# Ideamart-NB-IoT-Air-Quality-Sensor-v1.net
KiCad netlist of a schematic drawn in EAGLE
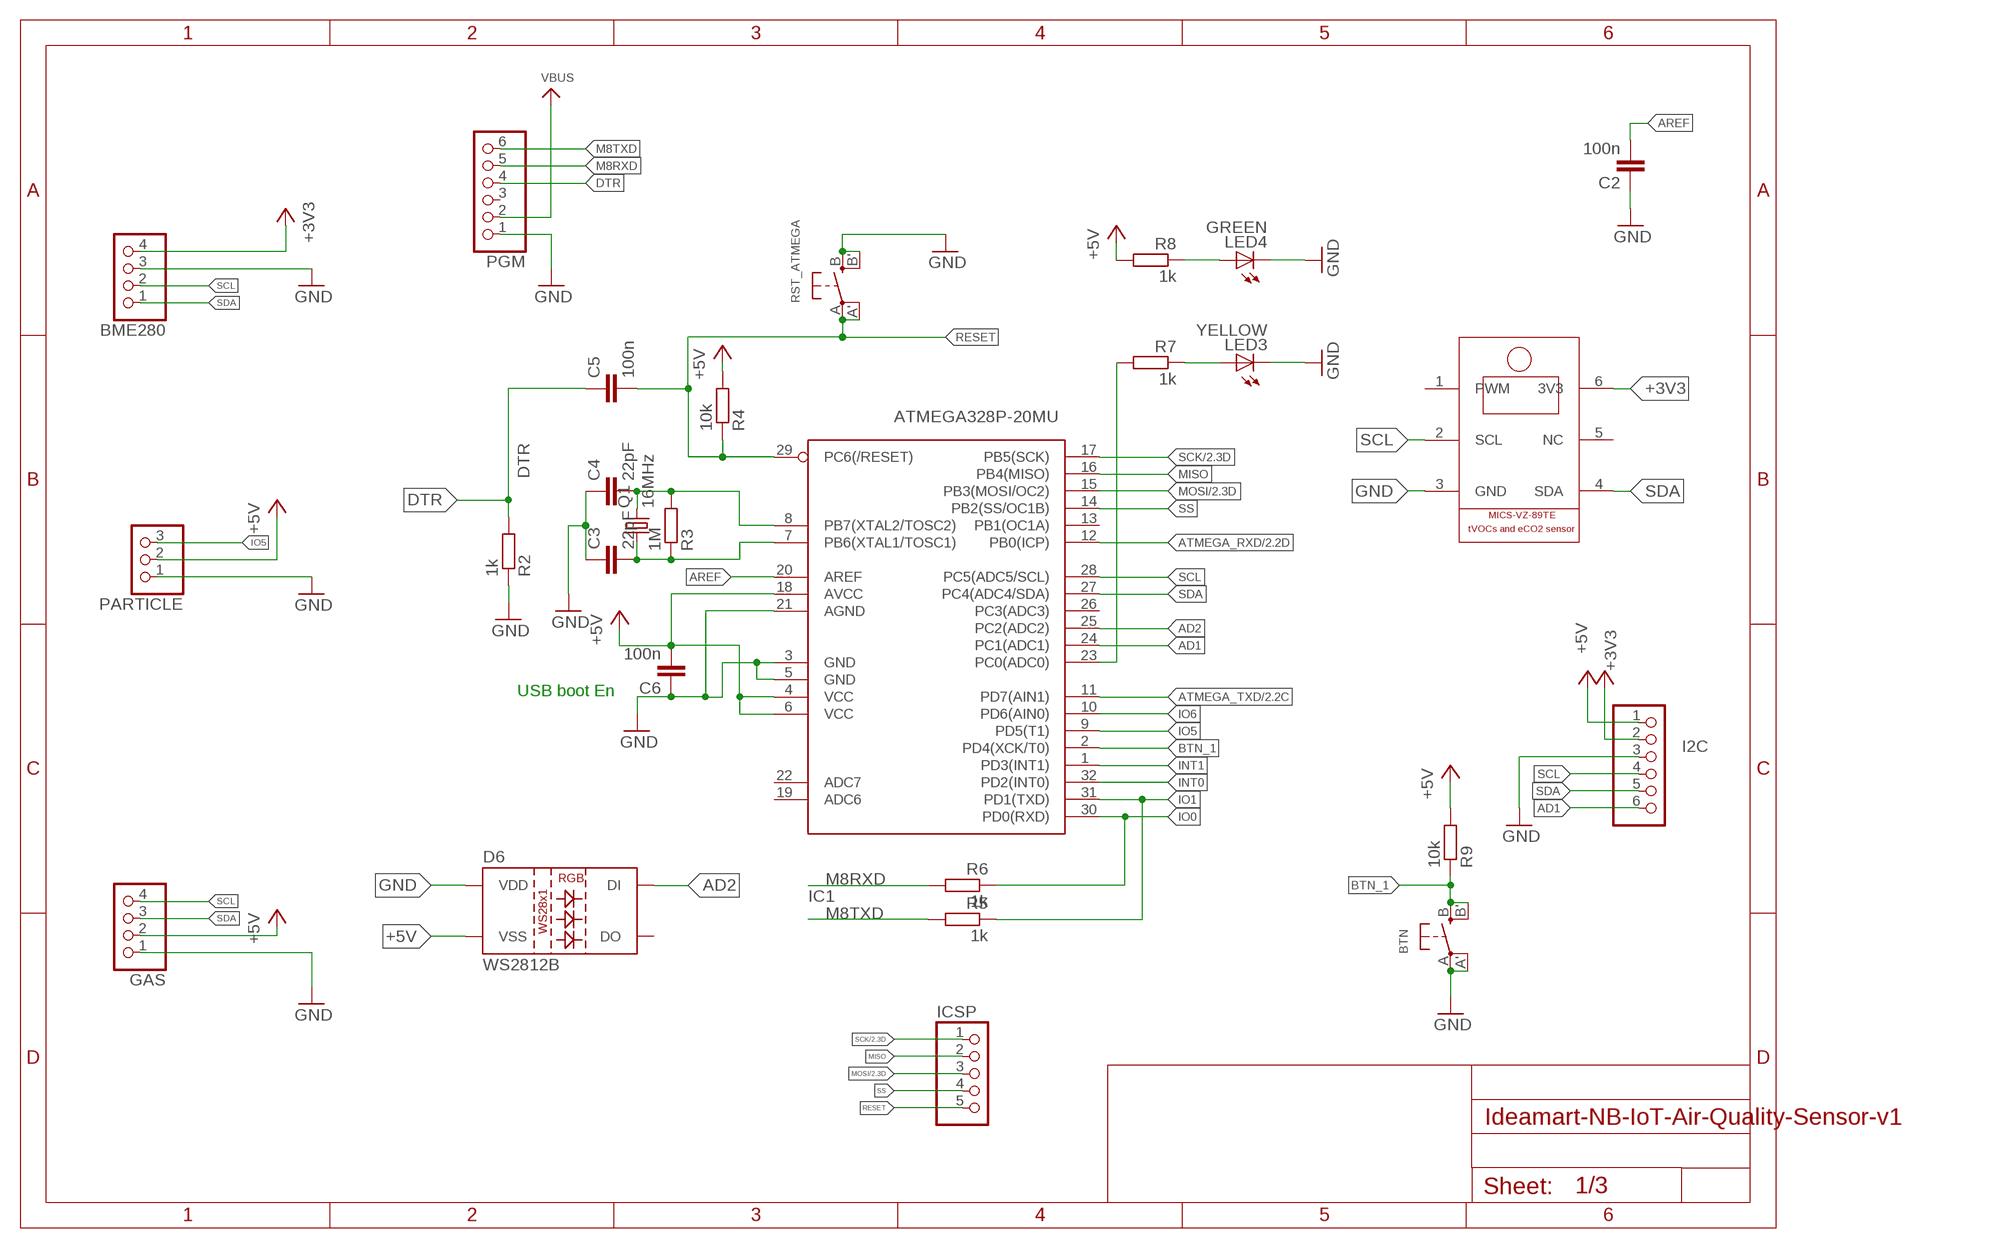
[diagram p0: schematic, sheet 1]
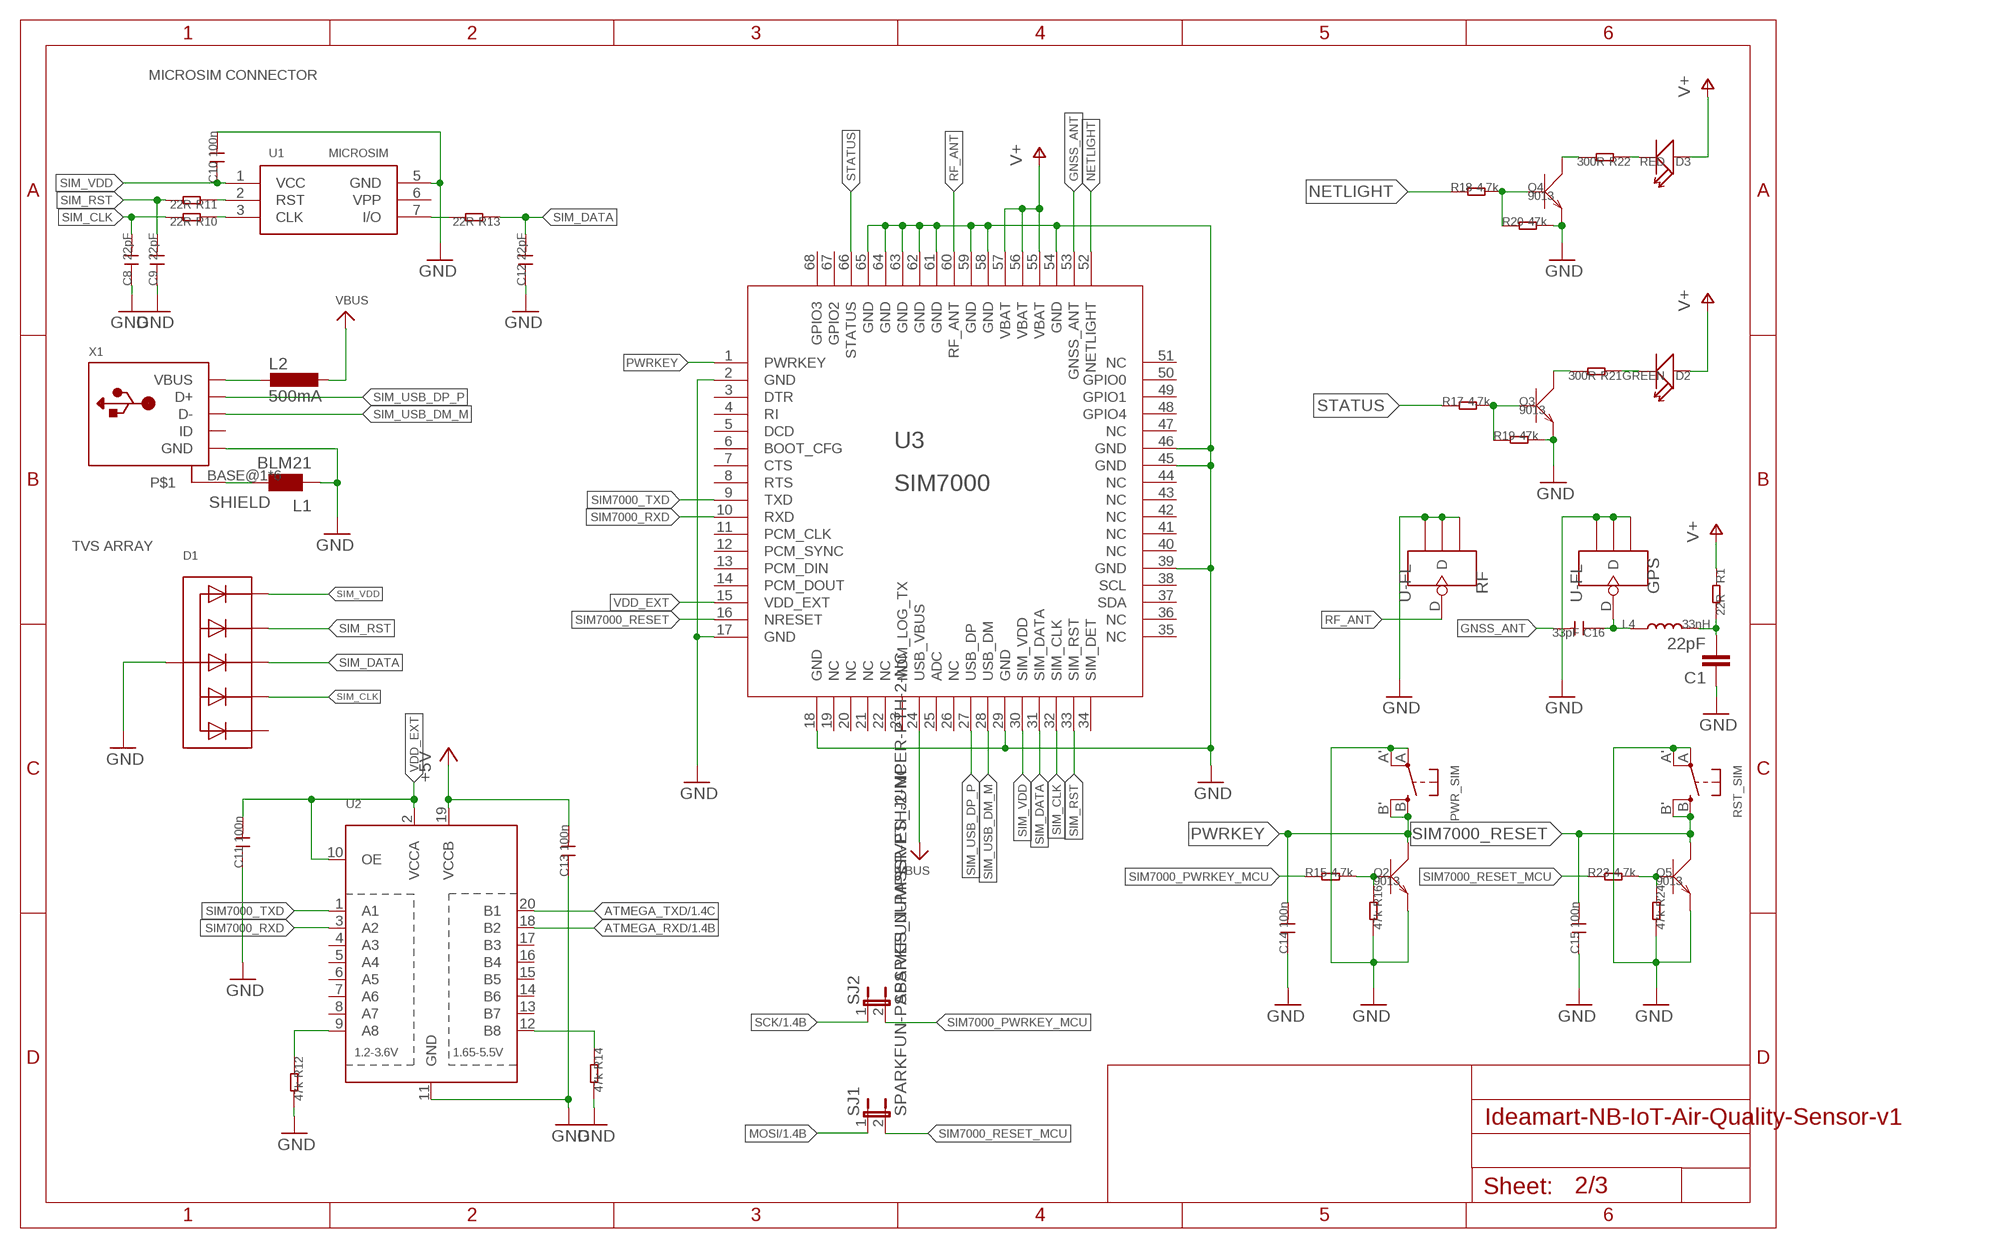
[diagram p1: schematic, sheet 2]
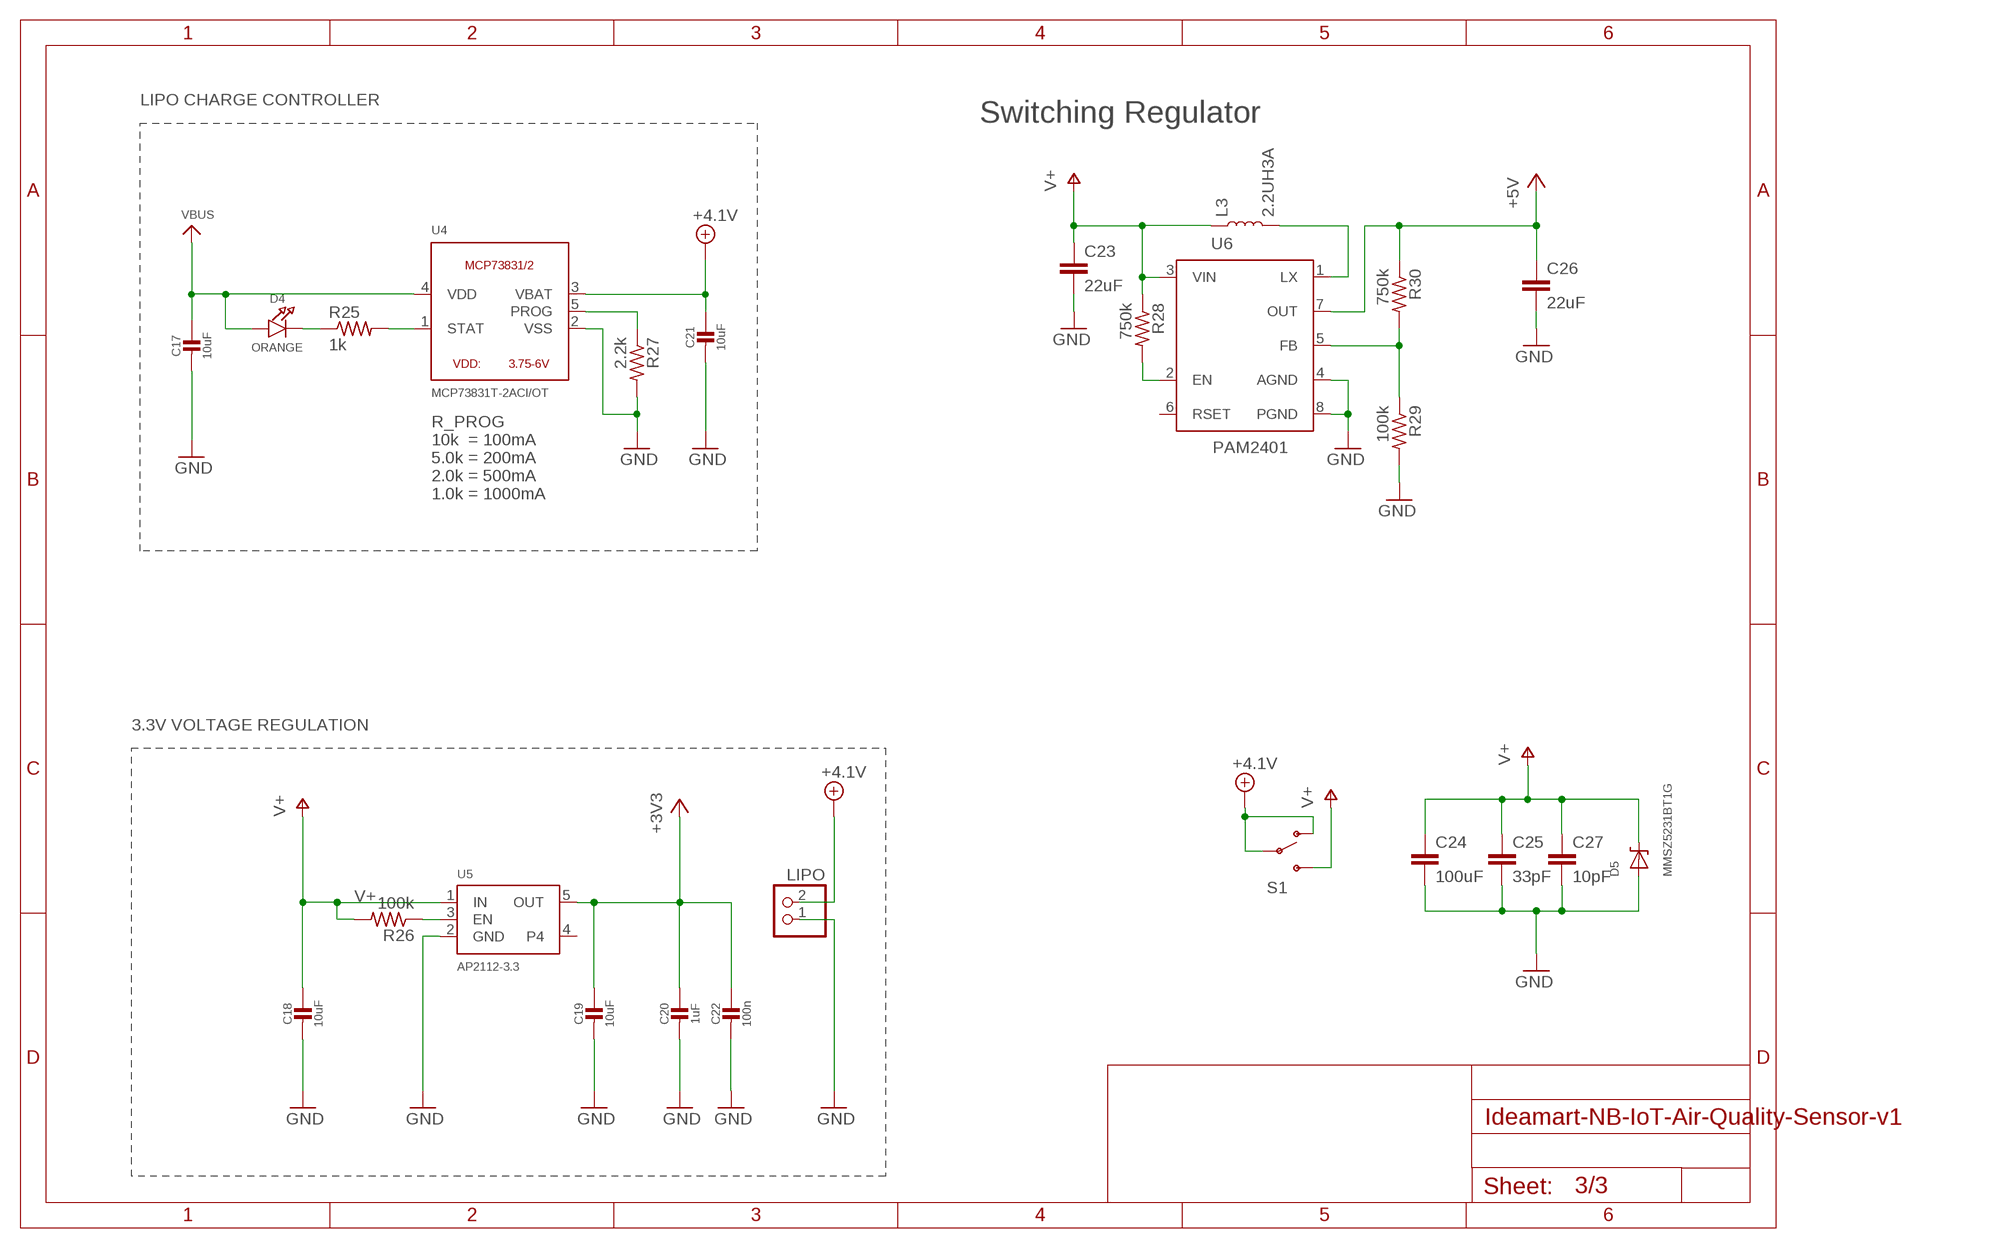
[diagram p2: schematic, sheet 3]

(export (version "E")
  (design (tool "Eeschema 10.0.6"))
  (components
    (comp (ref "BME280")
      (value "PINHD-1X4")
      (footprint "eagle-import:1X04")
      (libsource (lib "eagle-import") (part "PINHD-1X4"))
    )
    (comp (ref "BTN")
      (value "SWITCH_TACT_SMT4.6X2.8")
      (footprint "eagle-import:BTN_KMR2_4.6X2.8")
      (libsource (lib "eagle-import") (part "SWITCH_TACT_SMT4.6X2.8"))
    )
    (comp (ref "C2")
      (value "100n")
      (footprint "eagle-import:C0805")
      (libsource (lib "eagle-import") (part "C-EUC0805"))
    )
    (comp (ref "C3")
      (value "22pF")
      (footprint "eagle-import:C0805")
      (libsource (lib "eagle-import") (part "C-EUC0805"))
    )
    (comp (ref "C4")
      (value "22pF")
      (footprint "eagle-import:C0805")
      (libsource (lib "eagle-import") (part "C-EUC0805"))
    )
    (comp (ref "C5")
      (value "100n")
      (footprint "eagle-import:C0805")
      (libsource (lib "eagle-import") (part "C-EUC0805"))
    )
    (comp (ref "C6")
      (value "100n")
      (footprint "eagle-import:C0805")
      (libsource (lib "eagle-import") (part "C-EUC0805"))
    )
    (comp (ref "D6")
      (value "WS2812B")
      (footprint "eagle-import:WS2812B")
      (libsource (lib "eagle-import") (part "WS2812B"))
    )
    (comp (ref "GAS")
      (value "PINHD-1X4")
      (footprint "eagle-import:1X04")
      (libsource (lib "eagle-import") (part "PINHD-1X4"))
    )
    (comp (ref "I2C")
      (value "PINHD-1X6")
      (footprint "eagle-import:1X06")
      (libsource (lib "eagle-import") (part "PINHD-1X6"))
    )
    (comp (ref "IC1")
      (value "ATMEGA328P-20MU")
      (footprint "eagle-import:TQFP32-08")
      (libsource (lib "eagle-import") (part "MEGA8-AI"))
    )
    (comp (ref "ICSP")
      (value "PINHD-1X5")
      (footprint "eagle-import:1X05")
      (libsource (lib "eagle-import") (part "PINHD-1X5"))
    )
    (comp (ref "LED3")
      (value "YELLOW")
      (footprint "eagle-import:CHIP-LED0805")
      (libsource (lib "eagle-import") (part "LEDCHIP-LED0805"))
    )
    (comp (ref "LED4")
      (value "GREEN")
      (footprint "eagle-import:CHIP-LED0805")
      (libsource (lib "eagle-import") (part "LEDCHIP-LED0805"))
    )
    (comp (ref "PARTICLE")
      (value "PINHD-1X3")
      (footprint "eagle-import:1X03")
      (libsource (lib "eagle-import") (part "PINHD-1X3"))
    )
    (comp (ref "PGM")
      (value "PINHD-1X6")
      (footprint "eagle-import:1X06")
      (libsource (lib "eagle-import") (part "PINHD-1X6"))
    )
    (comp (ref "Q1")
      (value "16MHz")
      (footprint "eagle-import:CTS406")
      (libsource (lib "eagle-import") (part "CRYSTALCTS406"))
    )
    (comp (ref "R2")
      (value "1k")
      (footprint "eagle-import:R0805")
      (libsource (lib "eagle-import") (part "R-EU_R0805"))
    )
    (comp (ref "R3")
      (value "1M")
      (footprint "eagle-import:R0805")
      (libsource (lib "eagle-import") (part "R-EU_R0805"))
    )
    (comp (ref "R4")
      (value "10k")
      (footprint "eagle-import:R0805")
      (libsource (lib "eagle-import") (part "R-EU_R0805"))
    )
    (comp (ref "R5")
      (value "1k")
      (footprint "eagle-import:R0805")
      (libsource (lib "eagle-import") (part "R-EU_R0805"))
    )
    (comp (ref "R6")
      (value "1k")
      (footprint "eagle-import:R0805")
      (libsource (lib "eagle-import") (part "R-EU_R0805"))
    )
    (comp (ref "R7")
      (value "1k")
      (footprint "eagle-import:R0805")
      (libsource (lib "eagle-import") (part "R-EU_R0805"))
    )
    (comp (ref "R8")
      (value "1k")
      (footprint "eagle-import:R0805")
      (libsource (lib "eagle-import") (part "R-EU_R0805"))
    )
    (comp (ref "R9")
      (value "10k")
      (footprint "eagle-import:R0805")
      (libsource (lib "eagle-import") (part "R-EU_R0805"))
    )
    (comp (ref "RST_ATMEGA")
      (value "SWITCH_TACT_SMT4.6X2.8")
      (footprint "eagle-import:BTN_KMR2_4.6X2.8")
      (libsource (lib "eagle-import") (part "SWITCH_TACT_SMT4.6X2.8"))
    )
    (comp (ref "U$1")
      (value "MICS-VZ-89TE")
      (footprint "eagle-import:MICS-VZ-89TE")
      (libsource (lib "eagle-import") (part "MICS-VZ-89TE"))
    )
    (comp (ref "C17")
      (value "10uF")
      (footprint "eagle-import:_0805")
      (libsource (lib "eagle-import") (part "CAP_CERAMIC_0805"))
    )
    (comp (ref "C18")
      (value "10uF")
      (footprint "eagle-import:_0805MP")
      (libsource (lib "eagle-import") (part "CAP_CERAMIC_0805MP"))
    )
    (comp (ref "C19")
      (value "10uF")
      (footprint "eagle-import:_0805MP")
      (libsource (lib "eagle-import") (part "CAP_CERAMIC_0805MP"))
    )
    (comp (ref "C20")
      (value "1uF")
      (footprint "eagle-import:_0805MP")
      (libsource (lib "eagle-import") (part "CAP_CERAMIC_0805MP"))
    )
    (comp (ref "C21")
      (value "10uF")
      (footprint "eagle-import:_0805")
      (libsource (lib "eagle-import") (part "CAP_CERAMIC_0805"))
    )
    (comp (ref "C22")
      (value "100n")
      (footprint "eagle-import:_0805MP")
      (libsource (lib "eagle-import") (part "CAP_CERAMIC_0805MP"))
    )
    (comp (ref "C23")
      (value "22uF")
      (footprint "eagle-import:0805")
      (libsource (lib "eagle-import") (part "22UF-0805-6.3V-20%"))
    )
    (comp (ref "C24")
      (value "100uF")
      (footprint "eagle-import:1210")
      (libsource (lib "eagle-import") (part "22UF-1210-16V-20%"))
    )
    (comp (ref "C25")
      (value "33pF")
      (footprint "eagle-import:0805")
      (libsource (lib "eagle-import") (part "22UF-0805-6.3V-20%"))
    )
    (comp (ref "C26")
      (value "22uF")
      (footprint "eagle-import:0805")
      (libsource (lib "eagle-import") (part "22UF-0805-6.3V-20%"))
    )
    (comp (ref "C27")
      (value "10pF")
      (footprint "eagle-import:0805")
      (libsource (lib "eagle-import") (part "22UF-0805-6.3V-20%"))
    )
    (comp (ref "D4")
      (value "ORANGE")
      (footprint "eagle-import:CHIPLED_0805")
      (libsource (lib "eagle-import") (part "LED0805"))
    )
    (comp (ref "D5")
      (value "MMSZ5231BT1G")
      (footprint "eagle-import:SOD-123")
      (libsource (lib "eagle-import") (part "DIODE-ZENERSOD123"))
    )
    (comp (ref "L3")
      (value "2.2UH3A")
      (footprint "eagle-import:INDUCTOR_4X4MM")
      (libsource (lib "eagle-import") (part "INDUCTOR-IFSC1515AHER2R2M01"))
    )
    (comp (ref "LIPO")
      (value "JST_2PIN-SMT")
      (footprint "eagle-import:JST-PH-2-SMT")
      (libsource (lib "eagle-import") (part "JST_2PIN-SMT"))
    )
    (comp (ref "R25")
      (value "1k")
      (footprint "eagle-import:M0805")
      (libsource (lib "eagle-import") (part "R-US_M0805"))
    )
    (comp (ref "R26")
      (value "100k")
      (footprint "eagle-import:M0805")
      (libsource (lib "eagle-import") (part "R-US_M0805"))
    )
    (comp (ref "R27")
      (value "2.2k")
      (footprint "eagle-import:M0805")
      (libsource (lib "eagle-import") (part "R-US_M0805"))
    )
    (comp (ref "R28")
      (value "750k")
      (footprint "eagle-import:M0805")
      (libsource (lib "eagle-import") (part "R-US_M0805"))
    )
    (comp (ref "R29")
      (value "100k")
      (footprint "eagle-import:M0805")
      (libsource (lib "eagle-import") (part "R-US_M0805"))
    )
    (comp (ref "R30")
      (value "750k")
      (footprint "eagle-import:M0805")
      (libsource (lib "eagle-import") (part "R-US_M0805"))
    )
    (comp (ref "S1")
      (value "SWITCH-SPDT-SMD-A")
      (footprint "eagle-import:SWITCH-SPST-SMD-A")
      (libsource (lib "eagle-import") (part "SWITCH-SPDT-SMD-A"))
    )
    (comp (ref "U4")
      (value "MCP73831T-2ACI/OT")
      (footprint "eagle-import:SOT23-5")
      (libsource (lib "eagle-import") (part "MCP73831/2"))
    )
    (comp (ref "U5")
      (value "AP2112-3.3")
      (footprint "eagle-import:SOT23-5")
      (libsource (lib "eagle-import") (part "VREG_SOT23-5"))
    )
    (comp (ref "U6")
      (value "PAM2401")
      (footprint "eagle-import:MSOP8")
      (libsource (lib "eagle-import") (part "PAM2401"))
    )
    (comp (ref "C1")
      (value "22pF")
      (footprint "eagle-import:C0805")
      (libsource (lib "eagle-import") (part "C-EUC0805"))
    )
    (comp (ref "C8")
      (value "22pF")
      (footprint "eagle-import:0805")
      (libsource (lib "eagle-import") (part "C-0805"))
    )
    (comp (ref "C9")
      (value "22pF")
      (footprint "eagle-import:0805")
      (libsource (lib "eagle-import") (part "C-0805"))
    )
    (comp (ref "C10")
      (value "100n")
      (footprint "eagle-import:0805")
      (libsource (lib "eagle-import") (part "C-0805"))
    )
    (comp (ref "C11")
      (value "100n")
      (footprint "eagle-import:0805")
      (libsource (lib "eagle-import") (part "C-0805"))
    )
    (comp (ref "C12")
      (value "22pF")
      (footprint "eagle-import:0805")
      (libsource (lib "eagle-import") (part "C-0805"))
    )
    (comp (ref "C13")
      (value "100n")
      (footprint "eagle-import:0805")
      (libsource (lib "eagle-import") (part "C-0805"))
    )
    (comp (ref "C14")
      (value "100n")
      (footprint "eagle-import:0805")
      (libsource (lib "eagle-import") (part "C-0805"))
    )
    (comp (ref "C15")
      (value "100n")
      (footprint "eagle-import:0805")
      (libsource (lib "eagle-import") (part "C-0805"))
    )
    (comp (ref "C16")
      (value "33pF")
      (footprint "eagle-import:0805")
      (libsource (lib "eagle-import") (part "C-0805"))
    )
    (comp (ref "D1")
      (value "TVSARRAY_5LANE")
      (footprint "eagle-import:SOT363")
      (libsource (lib "eagle-import") (part "TVSARRAY_5LANE"))
    )
    (comp (ref "D2")
      (value "GREEN")
      (footprint "eagle-import:LED-0805")
      (libsource (lib "eagle-import") (part "LED'0805'"))
    )
    (comp (ref "D3")
      (value "RED")
      (footprint "eagle-import:LED-0805")
      (libsource (lib "eagle-import") (part "LED'0805'"))
    )
    (comp (ref "GPS")
      (value "U-FL")
      (footprint "eagle-import:4P-U-FL")
      (libsource (lib "eagle-import") (part "ANTENNA-U-FL"))
    )
    (comp (ref "L1")
      (value "BLM21")
      (footprint "eagle-import:0805")
      (libsource (lib "eagle-import") (part "WE-CBF_0805"))
    )
    (comp (ref "L2")
      (value "500mA")
      (footprint "eagle-import:L1812")
      (libsource (lib "eagle-import") (part "L-EUL1812"))
    )
    (comp (ref "L4")
      (value "33nH")
      (footprint "eagle-import:L0805")
      (libsource (lib "eagle-import") (part "L0805"))
    )
    (comp (ref "PWR_SIM")
      (value "SWITCH_TACT_SMT4.6X2.8")
      (footprint "eagle-import:BTN_KMR2_4.6X2.8")
      (libsource (lib "eagle-import") (part "SWITCH_TACT_SMT4.6X2.8"))
    )
    (comp (ref "Q2")
      (value "9013")
      (footprint "eagle-import:SOT23")
      (libsource (lib "eagle-import") (part "TRANSISTOR-NPN-SOT23"))
    )
    (comp (ref "Q3")
      (value "9013")
      (footprint "eagle-import:SOT23")
      (libsource (lib "eagle-import") (part "TRANSISTOR-NPN-SOT23"))
    )
    (comp (ref "Q4")
      (value "9013")
      (footprint "eagle-import:SOT23")
      (libsource (lib "eagle-import") (part "TRANSISTOR-NPN-SOT23"))
    )
    (comp (ref "Q5")
      (value "9013")
      (footprint "eagle-import:SOT23")
      (libsource (lib "eagle-import") (part "TRANSISTOR-NPN-SOT23"))
    )
    (comp (ref "R1")
      (value "22R")
      (footprint "eagle-import:0805")
      (libsource (lib "eagle-import") (part "R-0805"))
    )
    (comp (ref "R10")
      (value "22R")
      (footprint "eagle-import:0805")
      (libsource (lib "eagle-import") (part "R-0805"))
    )
    (comp (ref "R11")
      (value "22R")
      (footprint "eagle-import:0805")
      (libsource (lib "eagle-import") (part "R-0805"))
    )
    (comp (ref "R12")
      (value "47k")
      (footprint "eagle-import:0805")
      (libsource (lib "eagle-import") (part "R-0805"))
    )
    (comp (ref "R13")
      (value "22R")
      (footprint "eagle-import:0805")
      (libsource (lib "eagle-import") (part "R-0805"))
    )
    (comp (ref "R14")
      (value "47k")
      (footprint "eagle-import:0805")
      (libsource (lib "eagle-import") (part "R-0805"))
    )
    (comp (ref "R15")
      (value "4.7k")
      (footprint "eagle-import:0805")
      (libsource (lib "eagle-import") (part "R-0805"))
    )
    (comp (ref "R16")
      (value "47k")
      (footprint "eagle-import:0805")
      (libsource (lib "eagle-import") (part "R-0805"))
    )
    (comp (ref "R17")
      (value "4.7k")
      (footprint "eagle-import:0805")
      (libsource (lib "eagle-import") (part "R-0805"))
    )
    (comp (ref "R18")
      (value "4.7k")
      (footprint "eagle-import:0805")
      (libsource (lib "eagle-import") (part "R-0805"))
    )
    (comp (ref "R19")
      (value "47k")
      (footprint "eagle-import:0805")
      (libsource (lib "eagle-import") (part "R-0805"))
    )
    (comp (ref "R20")
      (value "47k")
      (footprint "eagle-import:0805")
      (libsource (lib "eagle-import") (part "R-0805"))
    )
    (comp (ref "R21")
      (value "300R")
      (footprint "eagle-import:0805")
      (libsource (lib "eagle-import") (part "R-0805"))
    )
    (comp (ref "R22")
      (value "300R")
      (footprint "eagle-import:0805")
      (libsource (lib "eagle-import") (part "R-0805"))
    )
    (comp (ref "R23")
      (value "4.7k")
      (footprint "eagle-import:0805")
      (libsource (lib "eagle-import") (part "R-0805"))
    )
    (comp (ref "R24")
      (value "47k")
      (footprint "eagle-import:0805")
      (libsource (lib "eagle-import") (part "R-0805"))
    )
    (comp (ref "RF")
      (value "U-FL")
      (footprint "eagle-import:4P-U-FL")
      (libsource (lib "eagle-import") (part "ANTENNA-U-FL"))
    )
    (comp (ref "RST_SIM")
      (value "SWITCH_TACT_SMT4.6X2.8")
      (footprint "eagle-import:BTN_KMR2_4.6X2.8")
      (libsource (lib "eagle-import") (part "SWITCH_TACT_SMT4.6X2.8"))
    )
    (comp (ref "SJ1")
      (value "SPARKFUN-PASSIVES_JUMPER-PTH-2-NC")
      (footprint "eagle-import:SPARKFUN-PASSIVES_PTH-JUMPER-NC_BOTTOM_NO_SILK")
      (libsource (lib "eagle-import") (part "SPARKFUN-PASSIVES_JUMPER-PTH-2-NC"))
    )
    (comp (ref "SJ2")
      (value "SPARKFUN-PASSIVES_JUMPER-PTH-2-NC")
      (footprint "eagle-import:SPARKFUN-PASSIVES_PTH-JUMPER-NC_BOTTOM_NO_SILK")
      (libsource (lib "eagle-import") (part "SPARKFUN-PASSIVES_JUMPER-PTH-2-NC"))
    )
    (comp (ref "U1")
      (value "MICROSIM")
      (footprint "eagle-import:MICROSIM")
      (libsource (lib "eagle-import") (part "MICROSIM"))
    )
    (comp (ref "U2")
      (value "TXB0108PWR")
      (footprint "eagle-import:TSSOP20")
      (libsource (lib "eagle-import") (part "TXB0108PWR"))
    )
    (comp (ref "U3")
      (value "SIM7000")
      (footprint "eagle-import:SIM7000")
      (libsource (lib "eagle-import") (part "SIM7000"))
    )
    (comp (ref "X1")
      (value "USB_MICRO_20329_V2")
      (footprint "eagle-import:4UCONN_20329_V2")
      (libsource (lib "eagle-import") (part "USB_MICRO_20329_V2"))
    )
  )
  (nets
    (net (code "1") (name "+3V3") (class "Default")
      (node (ref "BME280") (pin "4") (pinfunction "4_4") (pintype "passive"))
      (node (ref "C19") (pin "1") (pinfunction "1_1") (pintype "passive"))
      (node (ref "C20") (pin "1") (pinfunction "1_1") (pintype "passive"))
      (node (ref "C22") (pin "1") (pinfunction "1_1") (pintype "passive"))
      (node (ref "I2C") (pin "2") (pinfunction "2_2") (pintype "passive"))
      (node (ref "U$1") (pin "6") (pinfunction "3V3_6") (pintype "bidirectional"))
      (node (ref "U5") (pin "5") (pinfunction "OUT_5") (pintype "power_in"))
    )
    (net (code "2") (name "+4.1V") (class "Default")
      (node (ref "C21") (pin "1") (pinfunction "1_1") (pintype "passive"))
      (node (ref "LIPO") (pin "2") (pinfunction "1_2") (pintype "passive"))
      (node (ref "S1") (pin "1") (pinfunction "O_1") (pintype "passive"))
      (node (ref "S1") (pin "2") (pinfunction "P_2") (pintype "passive"))
      (node (ref "U4") (pin "3") (pinfunction "VBAT_3") (pintype "power_in"))
    )
    (net (code "3") (name "+5V") (class "Default")
      (node (ref "C13") (pin "2") (pinfunction "2_2") (pintype "passive"))
      (node (ref "C26") (pin "1") (pinfunction "1_1") (pintype "passive"))
      (node (ref "C6") (pin "2") (pinfunction "2_2") (pintype "passive"))
      (node (ref "D6") (pin "3") (pinfunction "VSS_3") (pintype "bidirectional"))
      (node (ref "GAS") (pin "2") (pinfunction "2_2") (pintype "passive"))
      (node (ref "I2C") (pin "1") (pinfunction "1_1") (pintype "passive"))
      (node (ref "IC1") (pin "18") (pinfunction "AVCC_18") (pintype "bidirectional"))
      (node (ref "IC1") (pin "4") (pinfunction "VCC_4") (pintype "bidirectional"))
      (node (ref "IC1") (pin "6") (pinfunction "VCC_6") (pintype "bidirectional"))
      (node (ref "PARTICLE") (pin "2") (pinfunction "2_2") (pintype "passive"))
      (node (ref "R30") (pin "1") (pinfunction "1_1") (pintype "passive"))
      (node (ref "R4") (pin "2") (pinfunction "2_2") (pintype "passive"))
      (node (ref "R8") (pin "2") (pinfunction "2_2") (pintype "passive"))
      (node (ref "R9") (pin "2") (pinfunction "2_2") (pintype "passive"))
      (node (ref "U2") (pin "19") (pinfunction "VCCB_19") (pintype "bidirectional"))
      (node (ref "U6") (pin "7") (pinfunction "OUT_7") (pintype "bidirectional"))
    )
    (net (code "4") (name "AD1") (class "Default")
      (node (ref "I2C") (pin "6") (pinfunction "6_6") (pintype "passive"))
      (node (ref "IC1") (pin "24") (pinfunction "PC1(ADC1)_24") (pintype "bidirectional"))
    )
    (net (code "5") (name "AD2") (class "Default")
      (node (ref "D6") (pin "4") (pinfunction "DI_4") (pintype "bidirectional"))
      (node (ref "IC1") (pin "25") (pinfunction "PC2(ADC2)_25") (pintype "bidirectional"))
    )
    (net (code "6") (name "AREF") (class "Default")
      (node (ref "C2") (pin "2") (pinfunction "2_2") (pintype "passive"))
      (node (ref "IC1") (pin "20") (pinfunction "AREF_20") (pintype "bidirectional"))
    )
    (net (code "7") (name "ATMEGA_RXD") (class "Default")
      (node (ref "IC1") (pin "12") (pinfunction "PB0(ICP)_12") (pintype "bidirectional"))
      (node (ref "U2") (pin "18") (pinfunction "B2_18") (pintype "bidirectional"))
    )
    (net (code "8") (name "ATMEGA_TXD") (class "Default")
      (node (ref "IC1") (pin "11") (pinfunction "PD7(AIN1)_11") (pintype "bidirectional"))
      (node (ref "U2") (pin "20") (pinfunction "B1_20") (pintype "bidirectional"))
    )
    (net (code "9") (name "BTN_1") (class "Default")
      (node (ref "BTN") (pin "B") (pinfunction "S_B") (pintype "passive"))
      (node (ref "BTN") (pin "B'") (pinfunction "S1_B'") (pintype "passive"))
      (node (ref "IC1") (pin "2") (pinfunction "PD4(XCK/T0)_2") (pintype "bidirectional"))
      (node (ref "R9") (pin "1") (pinfunction "1_1") (pintype "passive"))
    )
    (net (code "10") (name "DTR") (class "Default")
      (node (ref "C5") (pin "1") (pinfunction "1_1") (pintype "passive"))
      (node (ref "PGM") (pin "4") (pinfunction "4_4") (pintype "passive"))
      (node (ref "R2") (pin "2") (pinfunction "2_2") (pintype "passive"))
    )
    (net (code "11") (name "GND") (class "Default")
      (node (ref "BME280") (pin "3") (pinfunction "3_3") (pintype "passive"))
      (node (ref "BTN") (pin "A") (pinfunction "P_A") (pintype "passive"))
      (node (ref "BTN") (pin "A'") (pinfunction "P1_A'") (pintype "passive"))
      (node (ref "C1") (pin "1") (pinfunction "1_1") (pintype "passive"))
      (node (ref "C10") (pin "2") (pinfunction "2_2") (pintype "passive"))
      (node (ref "C11") (pin "1") (pinfunction "1_1") (pintype "passive"))
      (node (ref "C12") (pin "1") (pinfunction "1_1") (pintype "passive"))
      (node (ref "C13") (pin "1") (pinfunction "1_1") (pintype "passive"))
      (node (ref "C14") (pin "1") (pinfunction "1_1") (pintype "passive"))
      (node (ref "C15") (pin "1") (pinfunction "1_1") (pintype "passive"))
      (node (ref "C17") (pin "2") (pinfunction "2_2") (pintype "passive"))
      (node (ref "C18") (pin "2") (pinfunction "2_2") (pintype "passive"))
      (node (ref "C19") (pin "2") (pinfunction "2_2") (pintype "passive"))
      (node (ref "C2") (pin "1") (pinfunction "1_1") (pintype "passive"))
      (node (ref "C20") (pin "2") (pinfunction "2_2") (pintype "passive"))
      (node (ref "C21") (pin "2") (pinfunction "2_2") (pintype "passive"))
      (node (ref "C22") (pin "2") (pinfunction "2_2") (pintype "passive"))
      (node (ref "C23") (pin "2") (pinfunction "2_2") (pintype "passive"))
      (node (ref "C24") (pin "2") (pinfunction "2_2") (pintype "passive"))
      (node (ref "C25") (pin "2") (pinfunction "2_2") (pintype "passive"))
      (node (ref "C26") (pin "2") (pinfunction "2_2") (pintype "passive"))
      (node (ref "C27") (pin "2") (pinfunction "2_2") (pintype "passive"))
      (node (ref "C3") (pin "1") (pinfunction "1_1") (pintype "passive"))
      (node (ref "C4") (pin "1") (pinfunction "1_1") (pintype "passive"))
      (node (ref "C6") (pin "1") (pinfunction "1_1") (pintype "passive"))
      (node (ref "C8") (pin "1") (pinfunction "1_1") (pintype "passive"))
      (node (ref "C9") (pin "1") (pinfunction "1_1") (pintype "passive"))
      (node (ref "D1") (pin "2") (pinfunction "A_2") (pintype "passive"))
      (node (ref "D5") (pin "A") (pinfunction "A_A") (pintype "passive"))
      (node (ref "D6") (pin "1") (pinfunction "VDD_1") (pintype "bidirectional"))
      (node (ref "GAS") (pin "1") (pinfunction "1_1") (pintype "passive"))
      (node (ref "GPS") (pin "GND1") (pinfunction "GND1_GND1") (pintype "bidirectional"))
      (node (ref "GPS") (pin "GND2") (pinfunction "GND2_GND2") (pintype "bidirectional"))
      (node (ref "GPS") (pin "GND3") (pinfunction "GND3_GND3") (pintype "bidirectional"))
      (node (ref "I2C") (pin "3") (pinfunction "3_3") (pintype "passive"))
      (node (ref "IC1") (pin "21") (pinfunction "AGND_21") (pintype "bidirectional"))
      (node (ref "IC1") (pin "3") (pinfunction "GND_3") (pintype "bidirectional"))
      (node (ref "IC1") (pin "5") (pinfunction "GND_5") (pintype "bidirectional"))
      (node (ref "L1") (pin "1") (pinfunction "1_1") (pintype "passive"))
      (node (ref "LED3") (pin "C") (pinfunction "C_C") (pintype "passive"))
      (node (ref "LED4") (pin "C") (pinfunction "C_C") (pintype "passive"))
      (node (ref "LIPO") (pin "1") (pinfunction "2_1") (pintype "passive"))
      (node (ref "PARTICLE") (pin "1") (pinfunction "1_1") (pintype "passive"))
      (node (ref "PGM") (pin "1") (pinfunction "1_1") (pintype "passive"))
      (node (ref "PWR_SIM") (pin "A") (pinfunction "P_A") (pintype "passive"))
      (node (ref "PWR_SIM") (pin "A'") (pinfunction "P1_A'") (pintype "passive"))
      (node (ref "Q2") (pin "2") (pinfunction "E_2") (pintype "passive"))
      (node (ref "Q3") (pin "2") (pinfunction "E_2") (pintype "passive"))
      (node (ref "Q4") (pin "2") (pinfunction "E_2") (pintype "passive"))
      (node (ref "Q5") (pin "2") (pinfunction "E_2") (pintype "passive"))
      (node (ref "R12") (pin "2") (pinfunction "2_2") (pintype "passive"))
      (node (ref "R14") (pin "2") (pinfunction "2_2") (pintype "passive"))
      (node (ref "R16") (pin "2") (pinfunction "2_2") (pintype "passive"))
      (node (ref "R19") (pin "2") (pinfunction "2_2") (pintype "passive"))
      (node (ref "R2") (pin "1") (pinfunction "1_1") (pintype "passive"))
      (node (ref "R20") (pin "2") (pinfunction "2_2") (pintype "passive"))
      (node (ref "R24") (pin "2") (pinfunction "2_2") (pintype "passive"))
      (node (ref "R27") (pin "2") (pinfunction "2_2") (pintype "passive"))
      (node (ref "R29") (pin "2") (pinfunction "2_2") (pintype "passive"))
      (node (ref "RF") (pin "GND1") (pinfunction "GND1_GND1") (pintype "bidirectional"))
      (node (ref "RF") (pin "GND2") (pinfunction "GND2_GND2") (pintype "bidirectional"))
      (node (ref "RF") (pin "GND3") (pinfunction "GND3_GND3") (pintype "bidirectional"))
      (node (ref "RST_ATMEGA") (pin "B") (pinfunction "S_B") (pintype "passive"))
      (node (ref "RST_ATMEGA") (pin "B'") (pinfunction "S1_B'") (pintype "passive"))
      (node (ref "RST_SIM") (pin "A") (pinfunction "P_A") (pintype "passive"))
      (node (ref "RST_SIM") (pin "A'") (pinfunction "P1_A'") (pintype "passive"))
      (node (ref "U$1") (pin "3") (pinfunction "GND_3") (pintype "bidirectional"))
      (node (ref "U1") (pin "5") (pinfunction "GND_5") (pintype "bidirectional"))
      (node (ref "U2") (pin "11") (pinfunction "GND_11") (pintype "bidirectional"))
      (node (ref "U3") (pin "17") (pinfunction "GND_17") (pintype "power_in"))
      (node (ref "U3") (pin "18") (pinfunction "GND_18") (pintype "power_in"))
      (node (ref "U3") (pin "2") (pinfunction "GND_2") (pintype "power_in"))
      (node (ref "U3") (pin "29") (pinfunction "GND_29") (pintype "power_in"))
      (node (ref "U3") (pin "39") (pinfunction "GND_39") (pintype "power_in"))
      (node (ref "U3") (pin "45") (pinfunction "GND_45") (pintype "power_in"))
      (node (ref "U3") (pin "46") (pinfunction "GND_46") (pintype "power_in"))
      (node (ref "U3") (pin "54") (pinfunction "GND_54") (pintype "power_in"))
      (node (ref "U3") (pin "58") (pinfunction "GND_58") (pintype "output"))
      (node (ref "U3") (pin "59") (pinfunction "GND_59") (pintype "bidirectional"))
      (node (ref "U3") (pin "61") (pinfunction "GND_61") (pintype "input"))
      (node (ref "U3") (pin "62") (pinfunction "GND_62") (pintype "output"))
      (node (ref "U3") (pin "63") (pinfunction "GND_63") (pintype "output"))
      (node (ref "U3") (pin "64") (pinfunction "GND_64") (pintype "input"))
      (node (ref "U3") (pin "65") (pinfunction "GND_65") (pintype "bidirectional"))
      (node (ref "U4") (pin "2") (pinfunction "VSS_2") (pintype "power_in"))
      (node (ref "U5") (pin "2") (pinfunction "GND_2") (pintype "power_in"))
      (node (ref "U6") (pin "4") (pinfunction "AGND_4") (pintype "bidirectional"))
      (node (ref "U6") (pin "8") (pinfunction "PGND_8") (pintype "bidirectional"))
      (node (ref "X1") (pin "GND") (pinfunction "GND_GND") (pintype "power_in"))
    )
    (net (code "12") (name "GNSS_ANT") (class "Default")
      (node (ref "C16") (pin "2") (pinfunction "2_2") (pintype "passive"))
      (node (ref "U3") (pin "53") (pinfunction "GNSS_ANT_53") (pintype "power_in"))
    )
    (net (code "13") (name "GPIO2") (class "Default")
      (node (ref "U3") (pin "67") (pinfunction "GPIO2_67") (pintype "power_in"))
    )
    (net (code "14") (name "GPIO3") (class "Default")
      (node (ref "U3") (pin "68") (pinfunction "GPIO3_68") (pintype "power_in"))
    )
    (net (code "15") (name "INT0") (class "Default")
      (node (ref "IC1") (pin "32") (pinfunction "PD2(INT0)_32") (pintype "bidirectional"))
    )
    (net (code "16") (name "INT1") (class "Default")
      (node (ref "IC1") (pin "1") (pinfunction "PD3(INT1)_1") (pintype "bidirectional"))
    )
    (net (code "17") (name "IO0") (class "Default")
      (node (ref "IC1") (pin "30") (pinfunction "PD0(RXD)_30") (pintype "bidirectional"))
      (node (ref "R6") (pin "1") (pinfunction "1_1") (pintype "passive"))
    )
    (net (code "18") (name "IO1") (class "Default")
      (node (ref "IC1") (pin "31") (pinfunction "PD1(TXD)_31") (pintype "bidirectional"))
      (node (ref "R5") (pin "1") (pinfunction "1_1") (pintype "passive"))
    )
    (net (code "19") (name "IO5") (class "Default")
      (node (ref "IC1") (pin "9") (pinfunction "PD5(T1)_9") (pintype "bidirectional"))
      (node (ref "PARTICLE") (pin "3") (pinfunction "3_3") (pintype "passive"))
    )
    (net (code "20") (name "IO6") (class "Default")
      (node (ref "IC1") (pin "10") (pinfunction "PD6(AIN0)_10") (pintype "bidirectional"))
    )
    (net (code "21") (name "M8RXD") (class "Default")
      (node (ref "PGM") (pin "5") (pinfunction "5_5") (pintype "passive"))
      (node (ref "R6") (pin "2") (pinfunction "2_2") (pintype "passive"))
    )
    (net (code "22") (name "M8TXD") (class "Default")
      (node (ref "PGM") (pin "6") (pinfunction "6_6") (pintype "passive"))
      (node (ref "R5") (pin "2") (pinfunction "2_2") (pintype "passive"))
    )
    (net (code "23") (name "MISO") (class "Default")
      (node (ref "IC1") (pin "16") (pinfunction "PB4(MISO)_16") (pintype "bidirectional"))
      (node (ref "ICSP") (pin "2") (pinfunction "2_2") (pintype "passive"))
    )
    (net (code "24") (name "MOSI") (class "Default")
      (node (ref "IC1") (pin "15") (pinfunction "PB3(MOSI/OC2)_15") (pintype "bidirectional"))
      (node (ref "ICSP") (pin "3") (pinfunction "3_3") (pintype "passive"))
      (node (ref "SJ1") (pin "1") (pinfunction "1_1") (pintype "passive"))
    )
    (net (code "25") (name "NETLIGHT") (class "Default")
      (node (ref "R18") (pin "1") (pinfunction "1_1") (pintype "passive"))
      (node (ref "U3") (pin "52") (pinfunction "NETLIGHT_52") (pintype "power_in"))
    )
    (net (code "26") (name "Net-(C1-Pad2)") (class "Default")
      (node (ref "C1") (pin "2") (pinfunction "2_2") (pintype "passive"))
      (node (ref "L4") (pin "2") (pinfunction "2_2") (pintype "passive"))
      (node (ref "R1") (pin "2") (pinfunction "2_2") (pintype "passive"))
    )
    (net (code "27") (name "Net-(C16-Pad1)") (class "Default")
      (node (ref "C16") (pin "1") (pinfunction "1_1") (pintype "passive"))
      (node (ref "GPS") (pin "D") (pinfunction "D_D") (pintype "bidirectional"))
      (node (ref "L4") (pin "1") (pinfunction "1_1") (pintype "passive"))
    )
    (net (code "28") (name "Net-(D2-Pad-)") (class "Default")
      (node (ref "D2") (pin "-") (pinfunction "-_-") (pintype "passive"))
      (node (ref "R21") (pin "1") (pinfunction "1_1") (pintype "passive"))
    )
    (net (code "29") (name "Net-(D3-Pad-)") (class "Default")
      (node (ref "D3") (pin "-") (pinfunction "-_-") (pintype "passive"))
      (node (ref "R22") (pin "1") (pinfunction "1_1") (pintype "passive"))
    )
    (net (code "30") (name "Net-(D4-PadC)") (class "Default")
      (node (ref "D4") (pin "C") (pinfunction "C_C") (pintype "passive"))
      (node (ref "R25") (pin "1") (pinfunction "1_1") (pintype "passive"))
    )
    (net (code "31") (name "Net-(IC1-PB6(XTAL1{slash}TOSC1))") (class "Default")
      (node (ref "C3") (pin "2") (pinfunction "2_2") (pintype "passive"))
      (node (ref "IC1") (pin "7") (pinfunction "PB6(XTAL1/TOSC1)_7") (pintype "bidirectional"))
      (node (ref "Q1") (pin "1") (pinfunction "1_1") (pintype "passive"))
      (node (ref "R3") (pin "1") (pinfunction "1_1") (pintype "passive"))
    )
    (net (code "32") (name "Net-(IC1-PB7(XTAL2{slash}TOSC2))") (class "Default")
      (node (ref "C4") (pin "2") (pinfunction "2_2") (pintype "passive"))
      (node (ref "IC1") (pin "8") (pinfunction "PB7(XTAL2/TOSC2)_8") (pintype "bidirectional"))
      (node (ref "Q1") (pin "3") (pinfunction "2_3") (pintype "passive"))
      (node (ref "R3") (pin "2") (pinfunction "2_2") (pintype "passive"))
    )
    (net (code "33") (name "Net-(IC1-PC0(ADC0))") (class "Default")
      (node (ref "IC1") (pin "23") (pinfunction "PC0(ADC0)_23") (pintype "bidirectional"))
      (node (ref "R7") (pin "2") (pinfunction "2_2") (pintype "passive"))
    )
    (net (code "34") (name "Net-(L2-Pad2)") (class "Default")
      (node (ref "L2") (pin "2") (pinfunction "2_2") (pintype "passive"))
      (node (ref "X1") (pin "VBUS") (pinfunction "VBUS_VBUS") (pintype "power_in"))
    )
    (net (code "35") (name "Net-(L3-2)") (class "Default")
      (node (ref "L3") (pin "P$2") (pinfunction "2_P$2") (pintype "passive"))
      (node (ref "U6") (pin "1") (pinfunction "LX_1") (pintype "bidirectional"))
    )
    (net (code "36") (name "Net-(LED3-PadA)") (class "Default")
      (node (ref "LED3") (pin "A") (pinfunction "A_A") (pintype "passive"))
      (node (ref "R7") (pin "1") (pinfunction "1_1") (pintype "passive"))
    )
    (net (code "37") (name "Net-(LED4-PadA)") (class "Default")
      (node (ref "LED4") (pin "A") (pinfunction "A_A") (pintype "passive"))
      (node (ref "R8") (pin "1") (pinfunction "1_1") (pintype "passive"))
    )
    (net (code "38") (name "Net-(Q2-B)") (class "Default")
      (node (ref "Q2") (pin "1") (pinfunction "B_1") (pintype "passive"))
      (node (ref "R15") (pin "2") (pinfunction "2_2") (pintype "passive"))
      (node (ref "R16") (pin "1") (pinfunction "1_1") (pintype "passive"))
    )
    (net (code "39") (name "Net-(Q3-B)") (class "Default")
      (node (ref "Q3") (pin "1") (pinfunction "B_1") (pintype "passive"))
      (node (ref "R17") (pin "2") (pinfunction "2_2") (pintype "passive"))
      (node (ref "R19") (pin "1") (pinfunction "1_1") (pintype "passive"))
    )
    (net (code "40") (name "Net-(Q3-C)") (class "Default")
      (node (ref "Q3") (pin "3") (pinfunction "C_3") (pintype "passive"))
      (node (ref "R21") (pin "2") (pinfunction "2_2") (pintype "passive"))
    )
    (net (code "41") (name "Net-(Q4-B)") (class "Default")
      (node (ref "Q4") (pin "1") (pinfunction "B_1") (pintype "passive"))
      (node (ref "R18") (pin "2") (pinfunction "2_2") (pintype "passive"))
      (node (ref "R20") (pin "1") (pinfunction "1_1") (pintype "passive"))
    )
    (net (code "42") (name "Net-(Q4-C)") (class "Default")
      (node (ref "Q4") (pin "3") (pinfunction "C_3") (pintype "passive"))
      (node (ref "R22") (pin "2") (pinfunction "2_2") (pintype "passive"))
    )
    (net (code "43") (name "Net-(Q5-B)") (class "Default")
      (node (ref "Q5") (pin "1") (pinfunction "B_1") (pintype "passive"))
      (node (ref "R23") (pin "2") (pinfunction "2_2") (pintype "passive"))
      (node (ref "R24") (pin "1") (pinfunction "1_1") (pintype "passive"))
    )
    (net (code "44") (name "Net-(U1-CLK)") (class "Default")
      (node (ref "R10") (pin "1") (pinfunction "1_1") (pintype "passive"))
      (node (ref "U1") (pin "3") (pinfunction "CLK_3") (pintype "bidirectional"))
    )
    (net (code "45") (name "Net-(U1-I{slash}O)") (class "Default")
      (node (ref "R13") (pin "2") (pinfunction "2_2") (pintype "passive"))
      (node (ref "U1") (pin "7") (pinfunction "I/O_7") (pintype "bidirectional"))
    )
    (net (code "46") (name "Net-(U1-RST)") (class "Default")
      (node (ref "R11") (pin "1") (pinfunction "1_1") (pintype "passive"))
      (node (ref "U1") (pin "2") (pinfunction "RST_2") (pintype "bidirectional"))
    )
    (net (code "47") (name "Net-(U2-A8)") (class "Default")
      (node (ref "R12") (pin "1") (pinfunction "1_1") (pintype "passive"))
      (node (ref "U2") (pin "9") (pinfunction "A8_9") (pintype "bidirectional"))
    )
    (net (code "48") (name "Net-(U2-B8)") (class "Default")
      (node (ref "R14") (pin "1") (pinfunction "1_1") (pintype "passive"))
      (node (ref "U2") (pin "12") (pinfunction "B8_12") (pintype "bidirectional"))
    )
    (net (code "49") (name "Net-(U4-PROG)") (class "Default")
      (node (ref "R27") (pin "1") (pinfunction "1_1") (pintype "passive"))
      (node (ref "U4") (pin "5") (pinfunction "PROG_5") (pintype "input"))
    )
    (net (code "50") (name "Net-(U4-STAT)") (class "Default")
      (node (ref "R25") (pin "2") (pinfunction "2_2") (pintype "passive"))
      (node (ref "U4") (pin "1") (pinfunction "STAT_1") (pintype "output"))
    )
    (net (code "51") (name "Net-(U5-EN)") (class "Default")
      (node (ref "R26") (pin "1") (pinfunction "1_1") (pintype "passive"))
      (node (ref "U5") (pin "3") (pinfunction "EN_3") (pintype "input"))
    )
    (net (code "52") (name "Net-(U6-EN)") (class "Default")
      (node (ref "R28") (pin "2") (pinfunction "2_2") (pintype "passive"))
      (node (ref "U6") (pin "2") (pinfunction "EN_2") (pintype "bidirectional"))
    )
    (net (code "53") (name "Net-(U6-FB)") (class "Default")
      (node (ref "R29") (pin "1") (pinfunction "1_1") (pintype "passive"))
      (node (ref "R30") (pin "2") (pinfunction "2_2") (pintype "passive"))
      (node (ref "U6") (pin "5") (pinfunction "FB_5") (pintype "bidirectional"))
    )
    (net (code "54") (name "PWRKEY") (class "Default")
      (node (ref "C14") (pin "2") (pinfunction "2_2") (pintype "passive"))
      (node (ref "PWR_SIM") (pin "B") (pinfunction "S_B") (pintype "passive"))
      (node (ref "PWR_SIM") (pin "B'") (pinfunction "S1_B'") (pintype "passive"))
      (node (ref "Q2") (pin "3") (pinfunction "C_3") (pintype "passive"))
      (node (ref "U3") (pin "1") (pinfunction "PWRKEY_1") (pintype "input"))
    )
    (net (code "55") (name "RESET") (class "Default")
      (node (ref "C5") (pin "2") (pinfunction "2_2") (pintype "passive"))
      (node (ref "IC1") (pin "29") (pinfunction "PC6(/RESET)_29") (pintype "bidirectional"))
      (node (ref "ICSP") (pin "5") (pinfunction "5_5") (pintype "passive"))
      (node (ref "R4") (pin "1") (pinfunction "1_1") (pintype "passive"))
      (node (ref "RST_ATMEGA") (pin "A") (pinfunction "P_A") (pintype "passive"))
      (node (ref "RST_ATMEGA") (pin "A'") (pinfunction "P1_A'") (pintype "passive"))
    )
    (net (code "56") (name "RF_ANT") (class "Default")
      (node (ref "RF") (pin "D") (pinfunction "D_D") (pintype "bidirectional"))
      (node (ref "U3") (pin "60") (pinfunction "RF_ANT_60") (pintype "power_in"))
    )
    (net (code "57") (name "SCK") (class "Default")
      (node (ref "IC1") (pin "17") (pinfunction "PB5(SCK)_17") (pintype "bidirectional"))
      (node (ref "ICSP") (pin "1") (pinfunction "1_1") (pintype "passive"))
      (node (ref "SJ2") (pin "1") (pinfunction "1_1") (pintype "passive"))
    )
    (net (code "58") (name "SCL") (class "Default")
      (node (ref "BME280") (pin "2") (pinfunction "2_2") (pintype "passive"))
      (node (ref "GAS") (pin "4") (pinfunction "4_4") (pintype "passive"))
      (node (ref "I2C") (pin "4") (pinfunction "4_4") (pintype "passive"))
      (node (ref "IC1") (pin "28") (pinfunction "PC5(ADC5/SCL)_28") (pintype "bidirectional"))
      (node (ref "U$1") (pin "2") (pinfunction "SCL_2") (pintype "bidirectional"))
    )
    (net (code "59") (name "SDA") (class "Default")
      (node (ref "BME280") (pin "1") (pinfunction "1_1") (pintype "passive"))
      (node (ref "GAS") (pin "3") (pinfunction "3_3") (pintype "passive"))
      (node (ref "I2C") (pin "5") (pinfunction "5_5") (pintype "passive"))
      (node (ref "IC1") (pin "27") (pinfunction "PC4(ADC4/SDA)_27") (pintype "bidirectional"))
      (node (ref "U$1") (pin "4") (pinfunction "SDA_4") (pintype "bidirectional"))
    )
    (net (code "60") (name "SHIELD") (class "Default")
      (node (ref "L1") (pin "2") (pinfunction "2_2") (pintype "passive"))
      (node (ref "X1") (pin "BASE@1") (pinfunction "P$1_BASE@1") (pintype "bidirectional"))
      (node (ref "X1") (pin "BASE@2") (pinfunction "P$1_BASE@2") (pintype "bidirectional"))
      (node (ref "X1") (pin "SPRT@1") (pinfunction "P$1_SPRT@1") (pintype "bidirectional"))
      (node (ref "X1") (pin "SPRT@2") (pinfunction "P$1_SPRT@2") (pintype "bidirectional"))
      (node (ref "X1") (pin "SPRT@3") (pinfunction "P$1_SPRT@3") (pintype "bidirectional"))
      (node (ref "X1") (pin "SPRT@4") (pinfunction "P$1_SPRT@4") (pintype "bidirectional"))
    )
    (net (code "61") (name "SIM7000_PWRKEY_MCU") (class "Default")
      (node (ref "R15") (pin "1") (pinfunction "1_1") (pintype "passive"))
      (node (ref "SJ2") (pin "2") (pinfunction "2_2") (pintype "passive"))
    )
    (net (code "62") (name "SIM7000_RESET") (class "Default")
      (node (ref "C15") (pin "2") (pinfunction "2_2") (pintype "passive"))
      (node (ref "Q5") (pin "3") (pinfunction "C_3") (pintype "passive"))
      (node (ref "RST_SIM") (pin "B") (pinfunction "S_B") (pintype "passive"))
      (node (ref "RST_SIM") (pin "B'") (pinfunction "S1_B'") (pintype "passive"))
      (node (ref "U3") (pin "16") (pinfunction "NRESET_16") (pintype "input"))
    )
    (net (code "63") (name "SIM7000_RESET_MCU") (class "Default")
      (node (ref "R23") (pin "1") (pinfunction "1_1") (pintype "passive"))
      (node (ref "SJ1") (pin "2") (pinfunction "2_2") (pintype "passive"))
    )
    (net (code "64") (name "SIM7000_RXD") (class "Default")
      (node (ref "U2") (pin "3") (pinfunction "A2_3") (pintype "bidirectional"))
      (node (ref "U3") (pin "10") (pinfunction "RXD_10") (pintype "input"))
    )
    (net (code "65") (name "SIM7000_TXD") (class "Default")
      (node (ref "U2") (pin "1") (pinfunction "A1_1") (pintype "bidirectional"))
      (node (ref "U3") (pin "9") (pinfunction "TXD_9") (pintype "output"))
    )
    (net (code "66") (name "SIM_CLK") (class "Default")
      (node (ref "C8") (pin "2") (pinfunction "2_2") (pintype "passive"))
      (node (ref "D1") (pin "5") (pinfunction "C4_5") (pintype "passive"))
      (node (ref "R10") (pin "2") (pinfunction "2_2") (pintype "passive"))
      (node (ref "U3") (pin "32") (pinfunction "SIM_CLK_32") (pintype "output"))
    )
    (net (code "67") (name "SIM_DATA") (class "Default")
      (node (ref "C12") (pin "2") (pinfunction "2_2") (pintype "passive"))
      (node (ref "D1") (pin "4") (pinfunction "C3_4") (pintype "passive"))
      (node (ref "R13") (pin "1") (pinfunction "1_1") (pintype "passive"))
      (node (ref "U3") (pin "31") (pinfunction "SIM_DATA_31") (pintype "output"))
    )
    (net (code "68") (name "SIM_RST") (class "Default")
      (node (ref "C9") (pin "2") (pinfunction "2_2") (pintype "passive"))
      (node (ref "D1") (pin "3") (pinfunction "C2_3") (pintype "passive"))
      (node (ref "R11") (pin "2") (pinfunction "2_2") (pintype "passive"))
      (node (ref "U3") (pin "33") (pinfunction "SIM_RST_33") (pintype "bidirectional"))
    )
    (net (code "69") (name "SIM_USB_DM_M") (class "Default")
      (node (ref "U3") (pin "28") (pinfunction "USB_DM_28") (pintype "output"))
      (node (ref "X1") (pin "D-") (pinfunction "D-_D-") (pintype "bidirectional"))
    )
    (net (code "70") (name "SIM_USB_DP_P") (class "Default")
      (node (ref "U3") (pin "27") (pinfunction "USB_DP_27") (pintype "bidirectional"))
      (node (ref "X1") (pin "D+") (pinfunction "D+_D+") (pintype "bidirectional"))
    )
    (net (code "71") (name "SIM_VDD") (class "Default")
      (node (ref "C10") (pin "1") (pinfunction "1_1") (pintype "passive"))
      (node (ref "D1") (pin "1") (pinfunction "C1_1") (pintype "passive"))
      (node (ref "U1") (pin "1") (pinfunction "VCC_1") (pintype "bidirectional"))
      (node (ref "U3") (pin "30") (pinfunction "SIM_VDD_30") (pintype "input"))
    )
    (net (code "72") (name "SS") (class "Default")
      (node (ref "IC1") (pin "14") (pinfunction "PB2(SS/OC1B)_14") (pintype "bidirectional"))
      (node (ref "ICSP") (pin "4") (pinfunction "4_4") (pintype "passive"))
    )
    (net (code "73") (name "STATUS") (class "Default")
      (node (ref "R17") (pin "1") (pinfunction "1_1") (pintype "passive"))
      (node (ref "U3") (pin "66") (pinfunction "STATUS_66") (pintype "power_in"))
    )
    (net (code "74") (name "V+") (class "Default")
      (node (ref "C18") (pin "1") (pinfunction "1_1") (pintype "passive"))
      (node (ref "C23") (pin "1") (pinfunction "1_1") (pintype "passive"))
      (node (ref "C24") (pin "1") (pinfunction "1_1") (pintype "passive"))
      (node (ref "C25") (pin "1") (pinfunction "1_1") (pintype "passive"))
      (node (ref "C27") (pin "1") (pinfunction "1_1") (pintype "passive"))
      (node (ref "D2") (pin "+") (pinfunction "+_+") (pintype "passive"))
      (node (ref "D3") (pin "+") (pinfunction "+_+") (pintype "passive"))
      (node (ref "D5") (pin "C") (pinfunction "C_C") (pintype "passive"))
      (node (ref "L3") (pin "P$1") (pinfunction "1_P$1") (pintype "passive"))
      (node (ref "R1") (pin "1") (pinfunction "1_1") (pintype "passive"))
      (node (ref "R26") (pin "2") (pinfunction "2_2") (pintype "passive"))
      (node (ref "R28") (pin "1") (pinfunction "1_1") (pintype "passive"))
      (node (ref "S1") (pin "3") (pinfunction "S_3") (pintype "passive"))
      (node (ref "U3") (pin "55") (pinfunction "VBAT_55") (pintype "power_in"))
      (node (ref "U3") (pin "56") (pinfunction "VBAT_56") (pintype "power_in"))
      (node (ref "U3") (pin "57") (pinfunction "VBAT_57") (pintype "power_in"))
      (node (ref "U5") (pin "1") (pinfunction "IN_1") (pintype "power_in"))
      (node (ref "U6") (pin "3") (pinfunction "VIN_3") (pintype "bidirectional"))
    )
    (net (code "75") (name "VBUS") (class "Default")
      (node (ref "C17") (pin "1") (pinfunction "1_1") (pintype "passive"))
      (node (ref "D4") (pin "A") (pinfunction "A_A") (pintype "passive"))
      (node (ref "L2") (pin "1") (pinfunction "1_1") (pintype "passive"))
      (node (ref "PGM") (pin "2") (pinfunction "2_2") (pintype "passive"))
      (node (ref "U3") (pin "24") (pinfunction "USB_VBUS_24") (pintype "output"))
      (node (ref "U4") (pin "4") (pinfunction "VDD_4") (pintype "power_in"))
    )
    (net (code "76") (name "VDD_EXT") (class "Default")
      (node (ref "C11") (pin "2") (pinfunction "2_2") (pintype "passive"))
      (node (ref "U2") (pin "10") (pinfunction "OE_10") (pintype "bidirectional"))
      (node (ref "U2") (pin "2") (pinfunction "VCCA_2") (pintype "bidirectional"))
      (node (ref "U3") (pin "15") (pinfunction "VDD_EXT_15") (pintype "output"))
    )
    (net (code "77") (name "unconnected-(D1-C5-Pad6)") (class "Default")
      (node (ref "D1") (pin "6") (pinfunction "C5_6") (pintype "passive"))
    )
    (net (code "78") (name "unconnected-(D6-DO-Pad2)") (class "Default")
      (node (ref "D6") (pin "2") (pinfunction "DO_2") (pintype "bidirectional"))
    )
    (net (code "79") (name "unconnected-(IC1-ADC6-Pad19)") (class "Default")
      (node (ref "IC1") (pin "19") (pinfunction "ADC6_19") (pintype "bidirectional"))
    )
    (net (code "80") (name "unconnected-(IC1-ADC7-Pad22)") (class "Default")
      (node (ref "IC1") (pin "22") (pinfunction "ADC7_22") (pintype "bidirectional"))
    )
    (net (code "81") (name "unconnected-(IC1-PB1(OC1A)-Pad13)") (class "Default")
      (node (ref "IC1") (pin "13") (pinfunction "PB1(OC1A)_13") (pintype "bidirectional"))
    )
    (net (code "82") (name "unconnected-(IC1-PC3(ADC3)-Pad26)") (class "Default")
      (node (ref "IC1") (pin "26") (pinfunction "PC3(ADC3)_26") (pintype "bidirectional"))
    )
    (net (code "83") (name "unconnected-(PGM-Pad3)") (class "Default")
      (node (ref "PGM") (pin "3") (pinfunction "3_3") (pintype "passive"))
    )
    (net (code "84") (name "unconnected-(U$1-NC-Pad5)") (class "Default")
      (node (ref "U$1") (pin "5") (pinfunction "NC_5") (pintype "bidirectional"))
    )
    (net (code "85") (name "unconnected-(U$1-PWM-Pad1)") (class "Default")
      (node (ref "U$1") (pin "1") (pinfunction "PWM_1") (pintype "bidirectional"))
    )
    (net (code "86") (name "unconnected-(U1-VPP-Pad6)") (class "Default")
      (node (ref "U1") (pin "6") (pinfunction "VPP_6") (pintype "bidirectional"))
    )
    (net (code "87") (name "unconnected-(U2-A3-Pad4)") (class "Default")
      (node (ref "U2") (pin "4") (pinfunction "A3_4") (pintype "bidirectional"))
    )
    (net (code "88") (name "unconnected-(U2-A4-Pad5)") (class "Default")
      (node (ref "U2") (pin "5") (pinfunction "A4_5") (pintype "bidirectional"))
    )
    (net (code "89") (name "unconnected-(U2-A5-Pad6)") (class "Default")
      (node (ref "U2") (pin "6") (pinfunction "A5_6") (pintype "bidirectional"))
    )
    (net (code "90") (name "unconnected-(U2-A6-Pad7)") (class "Default")
      (node (ref "U2") (pin "7") (pinfunction "A6_7") (pintype "bidirectional"))
    )
    (net (code "91") (name "unconnected-(U2-A7-Pad8)") (class "Default")
      (node (ref "U2") (pin "8") (pinfunction "A7_8") (pintype "bidirectional"))
    )
    (net (code "92") (name "unconnected-(U2-B3-Pad17)") (class "Default")
      (node (ref "U2") (pin "17") (pinfunction "B3_17") (pintype "bidirectional"))
    )
    (net (code "93") (name "unconnected-(U2-B4-Pad16)") (class "Default")
      (node (ref "U2") (pin "16") (pinfunction "B4_16") (pintype "bidirectional"))
    )
    (net (code "94") (name "unconnected-(U2-B5-Pad15)") (class "Default")
      (node (ref "U2") (pin "15") (pinfunction "B5_15") (pintype "bidirectional"))
    )
    (net (code "95") (name "unconnected-(U2-B6-Pad14)") (class "Default")
      (node (ref "U2") (pin "14") (pinfunction "B6_14") (pintype "bidirectional"))
    )
    (net (code "96") (name "unconnected-(U2-B7-Pad13)") (class "Default")
      (node (ref "U2") (pin "13") (pinfunction "B7_13") (pintype "bidirectional"))
    )
    (net (code "97") (name "unconnected-(U3-ADC-Pad25)") (class "Default")
      (node (ref "U3") (pin "25") (pinfunction "ADC_25") (pintype "input"))
    )
    (net (code "98") (name "unconnected-(U3-BOOT_CFG-Pad6)") (class "Default")
      (node (ref "U3") (pin "6") (pinfunction "BOOT_CFG_6") (pintype "output"))
    )
    (net (code "99") (name "unconnected-(U3-CTS-Pad7)") (class "Default")
      (node (ref "U3") (pin "7") (pinfunction "CTS_7") (pintype "output"))
    )
    (net (code "100") (name "unconnected-(U3-DCD-Pad5)") (class "Default")
      (node (ref "U3") (pin "5") (pinfunction "DCD_5") (pintype "output"))
    )
    (net (code "101") (name "unconnected-(U3-DTR-Pad3)") (class "Default")
      (node (ref "U3") (pin "3") (pinfunction "DTR_3") (pintype "input"))
    )
    (net (code "102") (name "unconnected-(U3-GPIO0-Pad50)") (class "Default")
      (node (ref "U3") (pin "50") (pinfunction "GPIO0_50") (pintype "bidirectional"))
    )
    (net (code "103") (name "unconnected-(U3-GPIO1-Pad49)") (class "Default")
      (node (ref "U3") (pin "49") (pinfunction "GPIO1_49") (pintype "bidirectional"))
    )
    (net (code "104") (name "unconnected-(U3-GPIO4-Pad48)") (class "Default")
      (node (ref "U3") (pin "48") (pinfunction "GPIO4_48") (pintype "input"))
    )
    (net (code "105") (name "unconnected-(U3-MDM_LOG_TX-Pad23)") (class "Default")
      (node (ref "U3") (pin "23") (pinfunction "MDM_LOG_TX_23") (pintype "input"))
    )
    (net (code "106") (name "unconnected-(U3-NC-Pad19)") (class "Default")
      (node (ref "U3") (pin "19") (pinfunction "NC_19") (pintype "input"))
    )
    (net (code "107") (name "unconnected-(U3-NC-Pad20)") (class "Default")
      (node (ref "U3") (pin "20") (pinfunction "NC_20") (pintype "output"))
    )
    (net (code "108") (name "unconnected-(U3-NC-Pad21)") (class "Default")
      (node (ref "U3") (pin "21") (pinfunction "NC_21") (pintype "output"))
    )
    (net (code "109") (name "unconnected-(U3-NC-Pad22)") (class "Default")
      (node (ref "U3") (pin "22") (pinfunction "NC_22") (pintype "input"))
    )
    (net (code "110") (name "unconnected-(U3-NC-Pad26)") (class "Default")
      (node (ref "U3") (pin "26") (pinfunction "NC_26") (pintype "output"))
    )
    (net (code "111") (name "unconnected-(U3-NC-Pad35)") (class "Default")
      (node (ref "U3") (pin "35") (pinfunction "NC_35") (pintype "input"))
    )
    (net (code "112") (name "unconnected-(U3-NC-Pad36)") (class "Default")
      (node (ref "U3") (pin "36") (pinfunction "NC_36") (pintype "output"))
    )
    (net (code "113") (name "unconnected-(U3-NC-Pad40)") (class "Default")
      (node (ref "U3") (pin "40") (pinfunction "NC_40") (pintype "output"))
    )
    (net (code "114") (name "unconnected-(U3-NC-Pad41)") (class "Default")
      (node (ref "U3") (pin "41") (pinfunction "NC_41") (pintype "output"))
    )
    (net (code "115") (name "unconnected-(U3-NC-Pad42)") (class "Default")
      (node (ref "U3") (pin "42") (pinfunction "NC_42") (pintype "output"))
    )
    (net (code "116") (name "unconnected-(U3-NC-Pad43)") (class "Default")
      (node (ref "U3") (pin "43") (pinfunction "NC_43") (pintype "output"))
    )
    (net (code "117") (name "unconnected-(U3-NC-Pad44)") (class "Default")
      (node (ref "U3") (pin "44") (pinfunction "NC_44") (pintype "output"))
    )
    (net (code "118") (name "unconnected-(U3-NC-Pad47)") (class "Default")
      (node (ref "U3") (pin "47") (pinfunction "NC_47") (pintype "input"))
    )
    (net (code "119") (name "unconnected-(U3-NC-Pad51)") (class "Default")
      (node (ref "U3") (pin "51") (pinfunction "NC_51") (pintype "bidirectional"))
    )
    (net (code "120") (name "unconnected-(U3-PCM_CLK-Pad11)") (class "Default")
      (node (ref "U3") (pin "11") (pinfunction "PCM_CLK_11") (pintype "output"))
    )
    (net (code "121") (name "unconnected-(U3-PCM_DIN-Pad13)") (class "Default")
      (node (ref "U3") (pin "13") (pinfunction "PCM_DIN_13") (pintype "output"))
    )
    (net (code "122") (name "unconnected-(U3-PCM_DOUT-Pad14)") (class "Default")
      (node (ref "U3") (pin "14") (pinfunction "PCM_DOUT_14") (pintype "output"))
    )
    (net (code "123") (name "unconnected-(U3-PCM_SYNC-Pad12)") (class "Default")
      (node (ref "U3") (pin "12") (pinfunction "PCM_SYNC_12") (pintype "bidirectional"))
    )
    (net (code "124") (name "unconnected-(U3-RI-Pad4)") (class "Default")
      (node (ref "U3") (pin "4") (pinfunction "RI_4") (pintype "output"))
    )
    (net (code "125") (name "unconnected-(U3-RTS-Pad8)") (class "Default")
      (node (ref "U3") (pin "8") (pinfunction "RTS_8") (pintype "input"))
    )
    (net (code "126") (name "unconnected-(U3-SCL-Pad38)") (class "Default")
      (node (ref "U3") (pin "38") (pinfunction "SCL_38") (pintype "output"))
    )
    (net (code "127") (name "unconnected-(U3-SDA-Pad37)") (class "Default")
      (node (ref "U3") (pin "37") (pinfunction "SDA_37") (pintype "bidirectional"))
    )
    (net (code "128") (name "unconnected-(U3-SIM_DET-Pad34)") (class "Default")
      (node (ref "U3") (pin "34") (pinfunction "SIM_DET_34") (pintype "bidirectional"))
    )
    (net (code "129") (name "unconnected-(U5-P4-Pad4)") (class "Default")
      (node (ref "U5") (pin "4") (pinfunction "P4_4") (pintype "bidirectional"))
    )
    (net (code "130") (name "unconnected-(U6-RSET-Pad6)") (class "Default")
      (node (ref "U6") (pin "6") (pinfunction "RSET_6") (pintype "bidirectional"))
    )
    (net (code "131") (name "unconnected-(X1-PadID)") (class "Default")
      (node (ref "X1") (pin "ID") (pinfunction "ID_ID") (pintype "bidirectional"))
    )
  )
)
